# H3BR61_Hardware.net
KiCad netlist of a schematic drawn in EAGLE
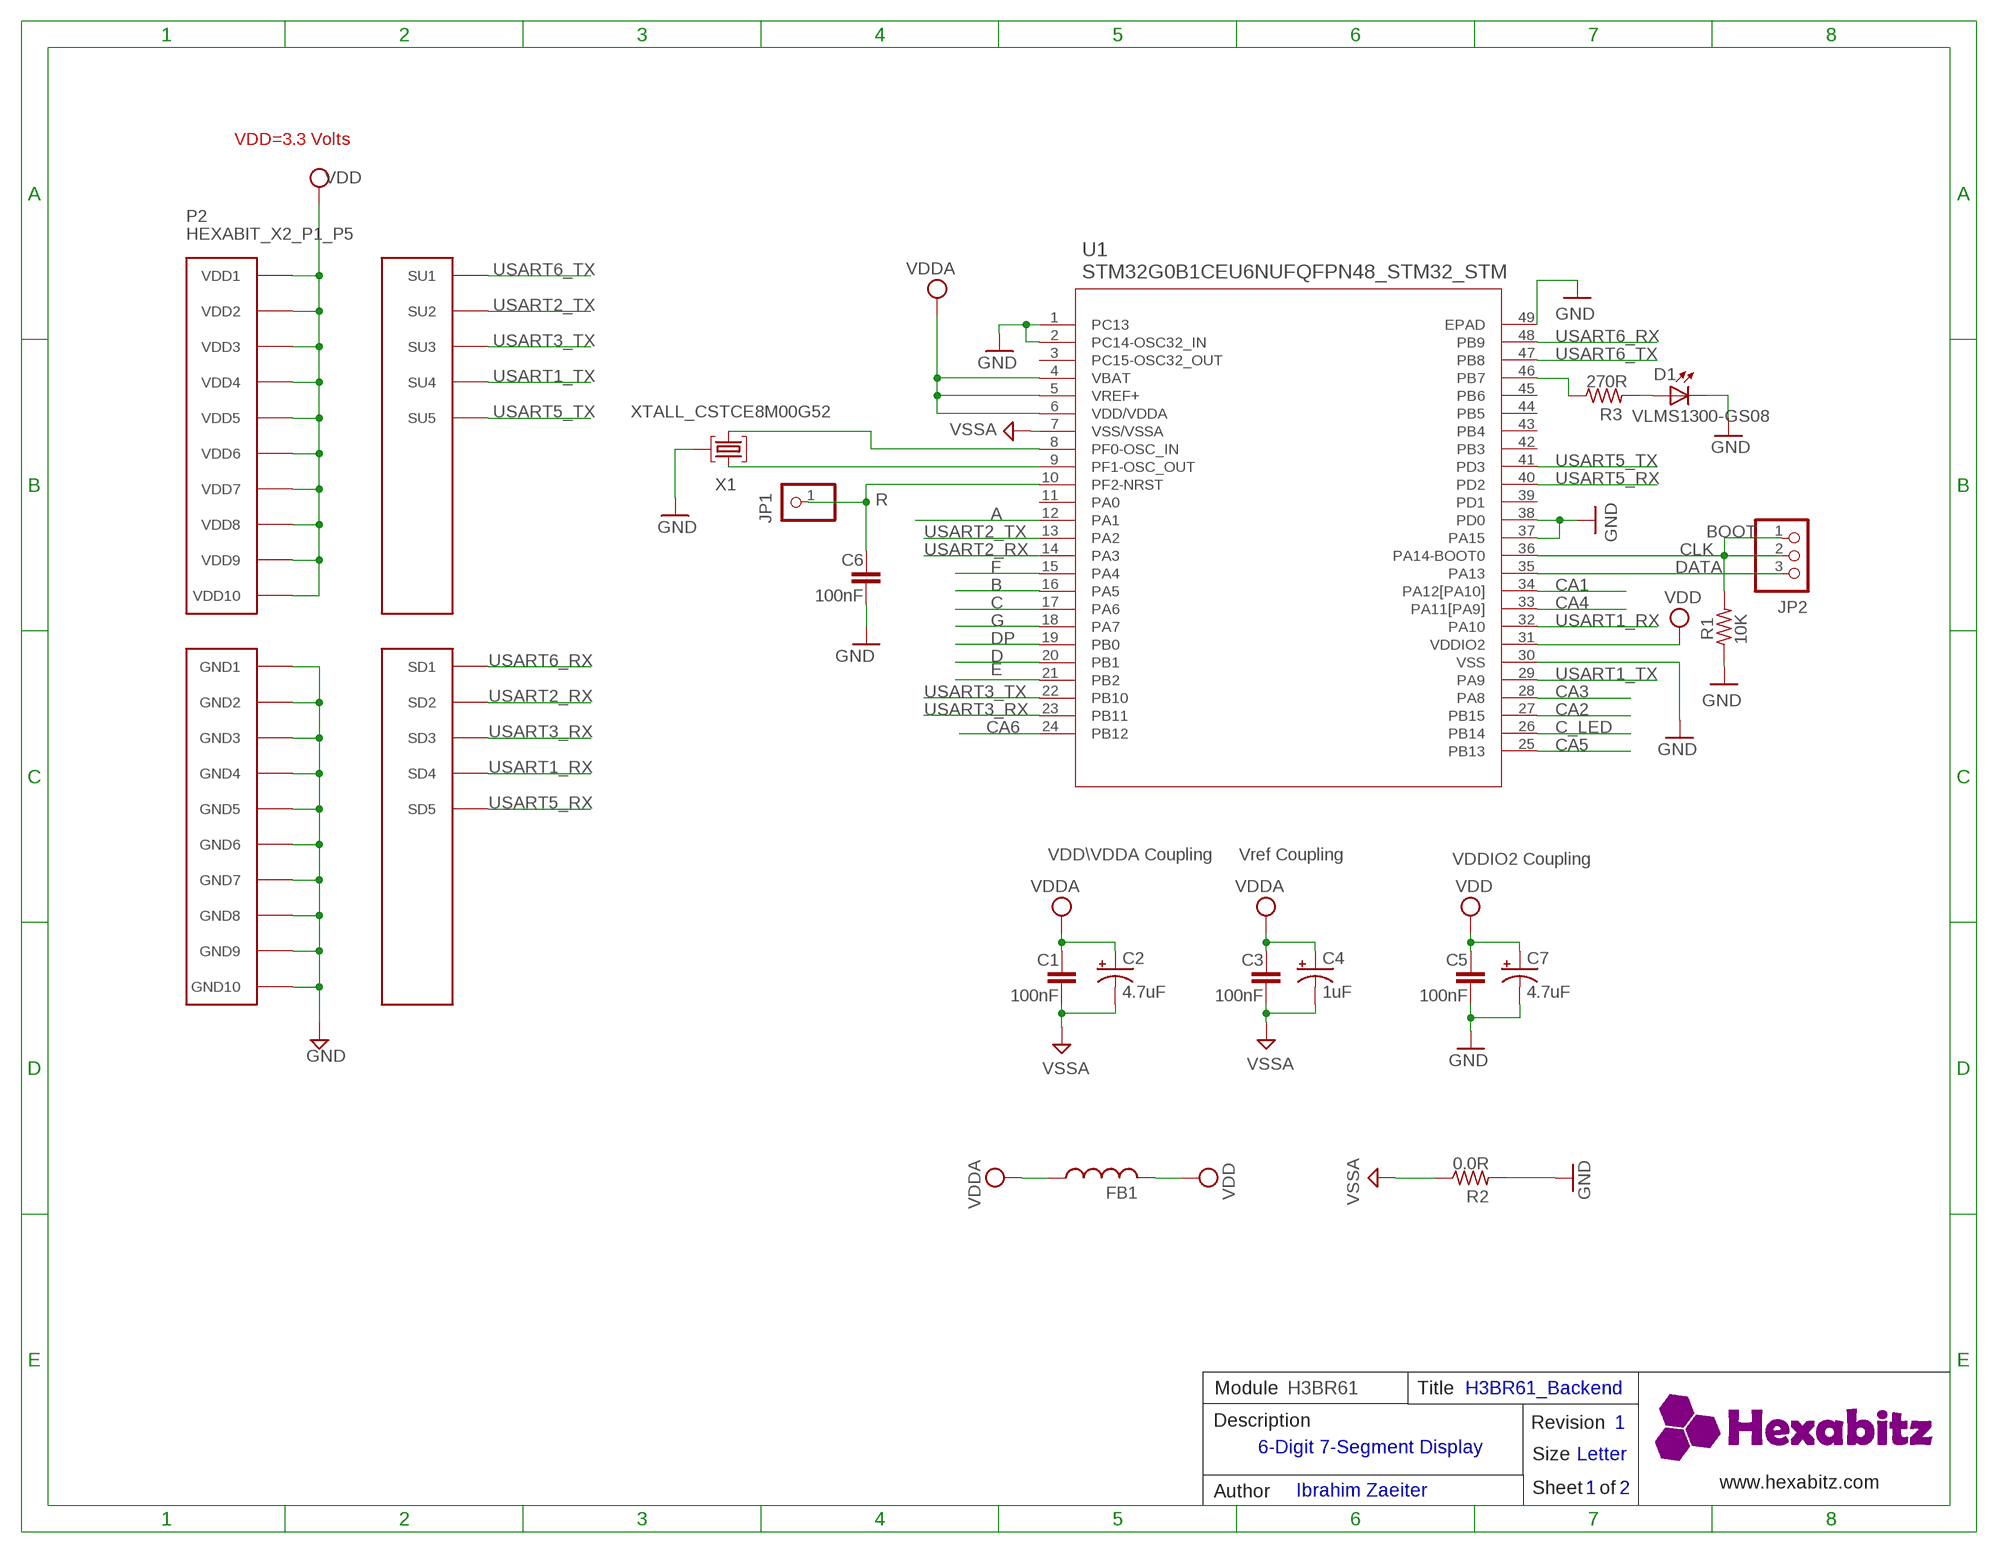
[diagram p0: schematic, sheet 1]
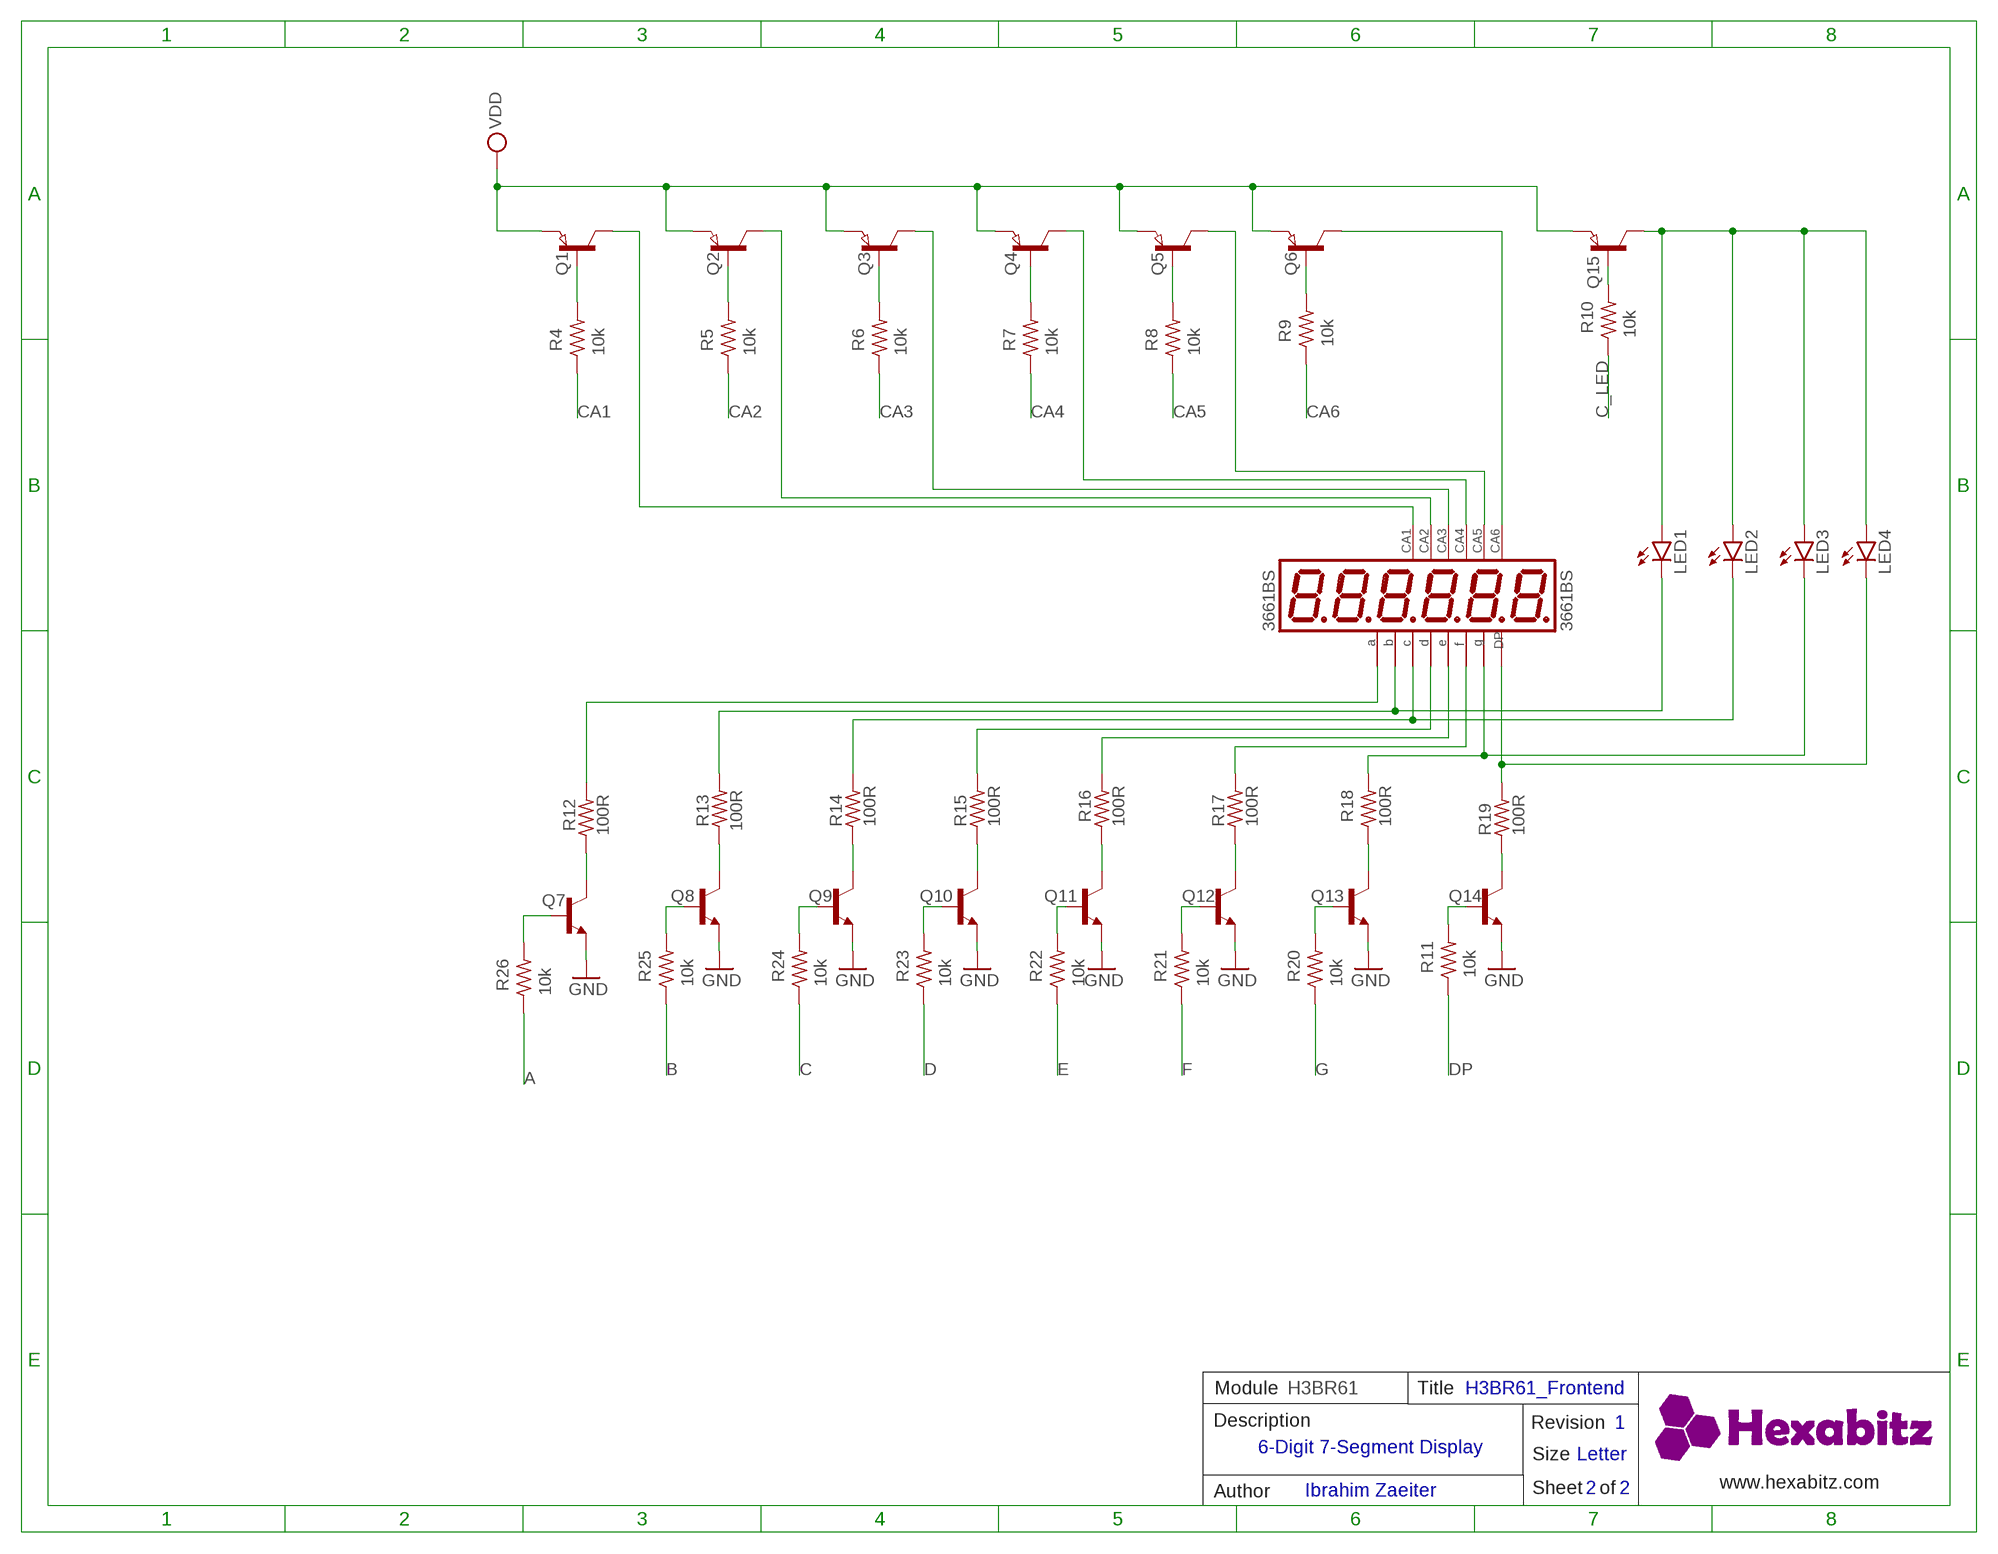
[diagram p1: schematic, sheet 2]

(export (version "E")
  (design (tool "Eeschema 10.0.6"))
  (components
    (comp (ref "C1")
      (value "100nF")
      (footprint "eagle-import:C-0603")
      (libsource (lib "eagle-import") (part "C-0603"))
    )
    (comp (ref "C2")
      (value "4.7uF")
      (footprint "eagle-import:C-0805-POL")
      (libsource (lib "eagle-import") (part "C-0805-POL"))
    )
    (comp (ref "C3")
      (value "100nF")
      (footprint "eagle-import:C-0603")
      (libsource (lib "eagle-import") (part "C-0603"))
    )
    (comp (ref "C4")
      (value "1uF")
      (footprint "eagle-import:C-0805-POL")
      (libsource (lib "eagle-import") (part "C-0805-POL"))
    )
    (comp (ref "C5")
      (value "100nF")
      (footprint "eagle-import:C-0603")
      (libsource (lib "eagle-import") (part "C-0603"))
    )
    (comp (ref "C6")
      (value "100nF")
      (footprint "eagle-import:C-0603")
      (libsource (lib "eagle-import") (part "C-0603"))
    )
    (comp (ref "C7")
      (value "4.7uF")
      (footprint "eagle-import:C-0805-POL")
      (libsource (lib "eagle-import") (part "C-0805-POL"))
    )
    (comp (ref "D1")
      (value "VLMS1300-GS08")
      (footprint "eagle-import:VLMS1300-GS08")
      (fields
        (field (name "MFN") "Vishay")
        (field (name "MPN") "VLMS1300-GS08")
        (field (name "OCTOPART_URL") "https://octopart.com/vlms1300-gs08-vishay-21709201?r=sp&s=_gcP4_q8T1SC6PJQPTQ9yA")
      )
      (libsource (lib "eagle-import") (part "VLMS1300-GS08"))
    )
    (comp (ref "FB1")
      (value "FB-0603")
      (footprint "eagle-import:FB-0603")
      (libsource (lib "eagle-import") (part "FB-0603"))
    )
    (comp (ref "JP1")
      (value "R")
      (footprint "eagle-import:1X01")
      (fields (field (name "MPN") "87227-1"))
      (libsource (lib "eagle-import") (part "PINHD-1X1"))
    )
    (comp (ref "JP2")
      (value "PINHD-1X3")
      (footprint "eagle-import:1X03")
      (libsource (lib "eagle-import") (part "PINHD-1X3"))
    )
    (comp (ref "P2")
      (value "HEXABIT_X2_P1_P5")
      (footprint "eagle-import:HEXABIT_17.32_X2_P1_P5")
      (libsource (lib "eagle-import") (part "HEXABIT_X2_P1_P5"))
    )
    (comp (ref "R1")
      (value "10K")
      (footprint "eagle-import:R-0603")
      (libsource (lib "eagle-import") (part "R-0603"))
    )
    (comp (ref "R2")
      (value "0.0R")
      (footprint "eagle-import:R-0603")
      (libsource (lib "eagle-import") (part "R-0603"))
    )
    (comp (ref "R3")
      (value "270R")
      (footprint "eagle-import:R-0603")
      (libsource (lib "eagle-import") (part "R-0603"))
    )
    (comp (ref "U1")
      (value "STM32G0B1CEU6NUFQFPN48_STM32_STM")
      (footprint "eagle-import:UFQFPN48_STM32_STM")
      (fields
        (field (name "MPN") "STM32G0B1CEU6N")
        (field (name "COPYRIGHT") "Copyright (C) 2022 Ultra Librarian. All rights reserved.")
      )
      (libsource (lib "eagle-import") (part "STM32G0B1CEU6NUFQFPN48_STM32_STM"))
    )
    (comp (ref "X1")
      (value "XTALL_CSTCE8M00G52")
      (footprint "eagle-import:XTALL_CSTCE8M00G52")
      (fields (field (name "MPN") "CSTCE8M00G52Z-R0"))
      (libsource (lib "eagle-import") (part "XTALL_CSTCE8M00G52"))
    )
    (comp (ref "3661BS")
      (value "3661BS")
      (footprint "eagle-import:3661BS")
      (libsource (lib "eagle-import") (part "3661BS"))
    )
    (comp (ref "LED1")
      (value "LED3MM")
      (footprint "eagle-import:LED3MM")
      (libsource (lib "eagle-import") (part "LED3MM"))
    )
    (comp (ref "LED2")
      (value "LED3MM")
      (footprint "eagle-import:LED3MM")
      (libsource (lib "eagle-import") (part "LED3MM"))
    )
    (comp (ref "LED3")
      (value "LED3MM")
      (footprint "eagle-import:LED3MM")
      (libsource (lib "eagle-import") (part "LED3MM"))
    )
    (comp (ref "LED4")
      (value "LED3MM")
      (footprint "eagle-import:LED3MM")
      (libsource (lib "eagle-import") (part "LED3MM"))
    )
    (comp (ref "Q1")
      (value "SEMICON-SMD-IPC_PNP-TRANSISTOR_SOT23")
      (footprint "eagle-import:SEMICON-SMD-IPC_SOT23")
      (libsource (lib "eagle-import") (part "SEMICON-SMD-IPC_PNP-TRANSISTOR_SOT23"))
    )
    (comp (ref "Q2")
      (value "SEMICON-SMD-IPC_PNP-TRANSISTOR_SOT23")
      (footprint "eagle-import:SEMICON-SMD-IPC_SOT23")
      (libsource (lib "eagle-import") (part "SEMICON-SMD-IPC_PNP-TRANSISTOR_SOT23"))
    )
    (comp (ref "Q3")
      (value "SEMICON-SMD-IPC_PNP-TRANSISTOR_SOT23")
      (footprint "eagle-import:SEMICON-SMD-IPC_SOT23")
      (libsource (lib "eagle-import") (part "SEMICON-SMD-IPC_PNP-TRANSISTOR_SOT23"))
    )
    (comp (ref "Q4")
      (value "SEMICON-SMD-IPC_PNP-TRANSISTOR_SOT23")
      (footprint "eagle-import:SEMICON-SMD-IPC_SOT23")
      (libsource (lib "eagle-import") (part "SEMICON-SMD-IPC_PNP-TRANSISTOR_SOT23"))
    )
    (comp (ref "Q5")
      (value "SEMICON-SMD-IPC_PNP-TRANSISTOR_SOT23")
      (footprint "eagle-import:SEMICON-SMD-IPC_SOT23")
      (libsource (lib "eagle-import") (part "SEMICON-SMD-IPC_PNP-TRANSISTOR_SOT23"))
    )
    (comp (ref "Q6")
      (value "SEMICON-SMD-IPC_PNP-TRANSISTOR_SOT23")
      (footprint "eagle-import:SEMICON-SMD-IPC_SOT23")
      (libsource (lib "eagle-import") (part "SEMICON-SMD-IPC_PNP-TRANSISTOR_SOT23"))
    )
    (comp (ref "Q7")
      (value "MMBT3904LT1")
      (footprint "eagle-import:MMBT3904LT1")
      (libsource (lib "eagle-import") (part "MMBT3904LT1"))
    )
    (comp (ref "Q8")
      (value "MMBT3904LT1")
      (footprint "eagle-import:MMBT3904LT1")
      (libsource (lib "eagle-import") (part "MMBT3904LT1"))
    )
    (comp (ref "Q9")
      (value "MMBT3904LT1")
      (footprint "eagle-import:MMBT3904LT1")
      (libsource (lib "eagle-import") (part "MMBT3904LT1"))
    )
    (comp (ref "Q10")
      (value "MMBT3904LT1")
      (footprint "eagle-import:MMBT3904LT1")
      (libsource (lib "eagle-import") (part "MMBT3904LT1"))
    )
    (comp (ref "Q11")
      (value "MMBT3904LT1")
      (footprint "eagle-import:MMBT3904LT1")
      (libsource (lib "eagle-import") (part "MMBT3904LT1"))
    )
    (comp (ref "Q12")
      (value "MMBT3904LT1")
      (footprint "eagle-import:MMBT3904LT1")
      (libsource (lib "eagle-import") (part "MMBT3904LT1"))
    )
    (comp (ref "Q13")
      (value "MMBT3904LT1")
      (footprint "eagle-import:MMBT3904LT1")
      (libsource (lib "eagle-import") (part "MMBT3904LT1"))
    )
    (comp (ref "Q14")
      (value "MMBT3904LT1")
      (footprint "eagle-import:MMBT3904LT1")
      (libsource (lib "eagle-import") (part "MMBT3904LT1"))
    )
    (comp (ref "Q15")
      (value "SEMICON-SMD-IPC_PNP-TRANSISTOR_SOT23")
      (footprint "eagle-import:SEMICON-SMD-IPC_SOT23")
      (libsource (lib "eagle-import") (part "SEMICON-SMD-IPC_PNP-TRANSISTOR_SOT23"))
    )
    (comp (ref "R4")
      (value "10k")
      (footprint "eagle-import:R-0603")
      (libsource (lib "eagle-import") (part "R-0603"))
    )
    (comp (ref "R5")
      (value "10k")
      (footprint "eagle-import:R-0603")
      (libsource (lib "eagle-import") (part "R-0603"))
    )
    (comp (ref "R6")
      (value "10k")
      (footprint "eagle-import:R-0603")
      (libsource (lib "eagle-import") (part "R-0603"))
    )
    (comp (ref "R7")
      (value "10k")
      (footprint "eagle-import:R-0603")
      (libsource (lib "eagle-import") (part "R-0603"))
    )
    (comp (ref "R8")
      (value "10k")
      (footprint "eagle-import:R-0603")
      (libsource (lib "eagle-import") (part "R-0603"))
    )
    (comp (ref "R9")
      (value "10k")
      (footprint "eagle-import:R-0603")
      (libsource (lib "eagle-import") (part "R-0603"))
    )
    (comp (ref "R10")
      (value "10k")
      (footprint "eagle-import:R-0603")
      (libsource (lib "eagle-import") (part "R-0603"))
    )
    (comp (ref "R11")
      (value "10k")
      (footprint "eagle-import:R-0603")
      (libsource (lib "eagle-import") (part "R-0603"))
    )
    (comp (ref "R12")
      (value "100R")
      (footprint "eagle-import:R-0603")
      (libsource (lib "eagle-import") (part "R-0603"))
    )
    (comp (ref "R13")
      (value "100R")
      (footprint "eagle-import:R-0603")
      (libsource (lib "eagle-import") (part "R-0603"))
    )
    (comp (ref "R14")
      (value "100R")
      (footprint "eagle-import:R-0603")
      (libsource (lib "eagle-import") (part "R-0603"))
    )
    (comp (ref "R15")
      (value "100R")
      (footprint "eagle-import:R-0603")
      (libsource (lib "eagle-import") (part "R-0603"))
    )
    (comp (ref "R16")
      (value "100R")
      (footprint "eagle-import:R-0603")
      (libsource (lib "eagle-import") (part "R-0603"))
    )
    (comp (ref "R17")
      (value "100R")
      (footprint "eagle-import:R-0603")
      (libsource (lib "eagle-import") (part "R-0603"))
    )
    (comp (ref "R18")
      (value "100R")
      (footprint "eagle-import:R-0603")
      (libsource (lib "eagle-import") (part "R-0603"))
    )
    (comp (ref "R19")
      (value "100R")
      (footprint "eagle-import:R-0603")
      (libsource (lib "eagle-import") (part "R-0603"))
    )
    (comp (ref "R20")
      (value "10k")
      (footprint "eagle-import:R-0603")
      (libsource (lib "eagle-import") (part "R-0603"))
    )
    (comp (ref "R21")
      (value "10k")
      (footprint "eagle-import:R-0603")
      (libsource (lib "eagle-import") (part "R-0603"))
    )
    (comp (ref "R22")
      (value "10k")
      (footprint "eagle-import:R-0603")
      (libsource (lib "eagle-import") (part "R-0603"))
    )
    (comp (ref "R23")
      (value "10k")
      (footprint "eagle-import:R-0603")
      (libsource (lib "eagle-import") (part "R-0603"))
    )
    (comp (ref "R24")
      (value "10k")
      (footprint "eagle-import:R-0603")
      (libsource (lib "eagle-import") (part "R-0603"))
    )
    (comp (ref "R25")
      (value "10k")
      (footprint "eagle-import:R-0603")
      (libsource (lib "eagle-import") (part "R-0603"))
    )
    (comp (ref "R26")
      (value "10k")
      (footprint "eagle-import:R-0603")
      (libsource (lib "eagle-import") (part "R-0603"))
    )
  )
  (nets
    (net (code "1") (name "A") (class "Default")
      (node (ref "R26") (pin "1") (pinfunction "1_1") (pintype "passive"))
      (node (ref "U1") (pin "12") (pinfunction "PA1_12") (pintype "bidirectional"))
    )
    (net (code "2") (name "B") (class "Default")
      (node (ref "R25") (pin "1") (pinfunction "1_1") (pintype "passive"))
      (node (ref "U1") (pin "16") (pinfunction "PA5_16") (pintype "bidirectional"))
    )
    (net (code "3") (name "C") (class "Default")
      (node (ref "R24") (pin "1") (pinfunction "1_1") (pintype "passive"))
      (node (ref "U1") (pin "17") (pinfunction "PA6_17") (pintype "bidirectional"))
    )
    (net (code "4") (name "CA1") (class "Default")
      (node (ref "R4") (pin "1") (pinfunction "1_1") (pintype "passive"))
      (node (ref "U1") (pin "34") (pinfunction "PA12[PA10]_34") (pintype "bidirectional"))
    )
    (net (code "5") (name "CA2") (class "Default")
      (node (ref "R5") (pin "1") (pinfunction "1_1") (pintype "passive"))
      (node (ref "U1") (pin "27") (pinfunction "PB15_27") (pintype "bidirectional"))
    )
    (net (code "6") (name "CA3") (class "Default")
      (node (ref "R6") (pin "1") (pinfunction "1_1") (pintype "passive"))
      (node (ref "U1") (pin "28") (pinfunction "PA8_28") (pintype "bidirectional"))
    )
    (net (code "7") (name "CA4") (class "Default")
      (node (ref "R7") (pin "1") (pinfunction "1_1") (pintype "passive"))
      (node (ref "U1") (pin "33") (pinfunction "PA11[PA9]_33") (pintype "bidirectional"))
    )
    (net (code "8") (name "CA5") (class "Default")
      (node (ref "R8") (pin "1") (pinfunction "1_1") (pintype "passive"))
      (node (ref "U1") (pin "25") (pinfunction "PB13_25") (pintype "bidirectional"))
    )
    (net (code "9") (name "CA6") (class "Default")
      (node (ref "R9") (pin "1") (pinfunction "1_1") (pintype "passive"))
      (node (ref "U1") (pin "24") (pinfunction "PB12_24") (pintype "bidirectional"))
    )
    (net (code "10") (name "CLK") (class "Default")
      (node (ref "JP2") (pin "1") (pinfunction "1_1") (pintype "passive"))
      (node (ref "JP2") (pin "2") (pinfunction "2_2") (pintype "passive"))
      (node (ref "R1") (pin "2") (pinfunction "2_2") (pintype "passive"))
      (node (ref "U1") (pin "36") (pinfunction "PA14-BOOT0_36") (pintype "bidirectional"))
    )
    (net (code "11") (name "C_LED") (class "Default")
      (node (ref "R10") (pin "1") (pinfunction "1_1") (pintype "passive"))
      (node (ref "U1") (pin "26") (pinfunction "PB14_26") (pintype "bidirectional"))
    )
    (net (code "12") (name "D") (class "Default")
      (node (ref "R23") (pin "1") (pinfunction "1_1") (pintype "passive"))
      (node (ref "U1") (pin "20") (pinfunction "PB1_20") (pintype "bidirectional"))
    )
    (net (code "13") (name "DATA") (class "Default")
      (node (ref "JP2") (pin "3") (pinfunction "3_3") (pintype "passive"))
      (node (ref "U1") (pin "35") (pinfunction "PA13_35") (pintype "bidirectional"))
    )
    (net (code "14") (name "DP") (class "Default")
      (node (ref "R11") (pin "1") (pinfunction "1_1") (pintype "passive"))
      (node (ref "U1") (pin "19") (pinfunction "PB0_19") (pintype "bidirectional"))
    )
    (net (code "15") (name "E") (class "Default")
      (node (ref "R22") (pin "1") (pinfunction "1_1") (pintype "passive"))
      (node (ref "U1") (pin "21") (pinfunction "PB2_21") (pintype "bidirectional"))
    )
    (net (code "16") (name "F") (class "Default")
      (node (ref "R21") (pin "1") (pinfunction "1_1") (pintype "passive"))
      (node (ref "U1") (pin "15") (pinfunction "PA4_15") (pintype "bidirectional"))
    )
    (net (code "17") (name "G") (class "Default")
      (node (ref "R20") (pin "1") (pinfunction "1_1") (pintype "passive"))
      (node (ref "U1") (pin "18") (pinfunction "PA7_18") (pintype "bidirectional"))
    )
    (net (code "18") (name "GND") (class "Default")
      (node (ref "C5") (pin "2") (pinfunction "2_2") (pintype "passive"))
      (node (ref "C6") (pin "2") (pinfunction "2_2") (pintype "passive"))
      (node (ref "C7") (pin "2") (pinfunction "-_2") (pintype "passive"))
      (node (ref "D1") (pin "C") (pinfunction "C_C") (pintype "passive"))
      (node (ref "P2") (pin "PAD_PD11") (pinfunction "GND1_PAD_PD11") (pintype "power_in"))
      (node (ref "P2") (pin "PAD_PD12") (pinfunction "GND2_PAD_PD12") (pintype "power_in"))
      (node (ref "P2") (pin "PAD_PD13") (pinfunction "GND3_PAD_PD13") (pintype "power_in"))
      (node (ref "P2") (pin "PAD_PD14") (pinfunction "GND4_PAD_PD14") (pintype "power_in"))
      (node (ref "P2") (pin "PAD_PD15") (pinfunction "GND5_PAD_PD15") (pintype "power_in"))
      (node (ref "P2") (pin "PAD_PD16") (pinfunction "GND6_PAD_PD16") (pintype "power_in"))
      (node (ref "P2") (pin "PAD_PD17") (pinfunction "GND7_PAD_PD17") (pintype "power_in"))
      (node (ref "P2") (pin "PAD_PD18") (pinfunction "GND8_PAD_PD18") (pintype "power_in"))
      (node (ref "P2") (pin "PAD_PD19") (pinfunction "GND9_PAD_PD19") (pintype "power_in"))
      (node (ref "P2") (pin "PAD_PD20") (pinfunction "GND10_PAD_PD20") (pintype "power_in"))
      (node (ref "Q10") (pin "2") (pinfunction "E_2") (pintype "passive"))
      (node (ref "Q11") (pin "2") (pinfunction "E_2") (pintype "passive"))
      (node (ref "Q12") (pin "2") (pinfunction "E_2") (pintype "passive"))
      (node (ref "Q13") (pin "2") (pinfunction "E_2") (pintype "passive"))
      (node (ref "Q14") (pin "2") (pinfunction "E_2") (pintype "passive"))
      (node (ref "Q7") (pin "2") (pinfunction "E_2") (pintype "passive"))
      (node (ref "Q8") (pin "2") (pinfunction "E_2") (pintype "passive"))
      (node (ref "Q9") (pin "2") (pinfunction "E_2") (pintype "passive"))
      (node (ref "R1") (pin "1") (pinfunction "1_1") (pintype "passive"))
      (node (ref "R2") (pin "2") (pinfunction "2_2") (pintype "passive"))
      (node (ref "U1") (pin "1") (pinfunction "PC13_1") (pintype "bidirectional"))
      (node (ref "U1") (pin "2") (pinfunction "PC14-OSC32_IN_2") (pintype "bidirectional"))
      (node (ref "U1") (pin "30") (pinfunction "VSS_30") (pintype "passive"))
      (node (ref "U1") (pin "37") (pinfunction "PA15_37") (pintype "bidirectional"))
      (node (ref "U1") (pin "38") (pinfunction "PD0_38") (pintype "bidirectional"))
      (node (ref "U1") (pin "49") (pinfunction "EPAD_49") (pintype "passive"))
      (node (ref "X1") (pin "P$2") (pinfunction "2_P$2") (pintype "passive"))
    )
    (net (code "19") (name "Net-(3661BS-A)") (class "Default")
      (node (ref "3661BS") (pin "13") (pinfunction "A_13") (pintype "passive"))
      (node (ref "R12") (pin "2") (pinfunction "2_2") (pintype "passive"))
    )
    (net (code "20") (name "Net-(3661BS-B)") (class "Default")
      (node (ref "3661BS") (pin "9") (pinfunction "B_9") (pintype "passive"))
      (node (ref "LED1") (pin "K") (pinfunction "C_K") (pintype "passive"))
      (node (ref "R13") (pin "2") (pinfunction "2_2") (pintype "passive"))
    )
    (net (code "21") (name "Net-(3661BS-C)") (class "Default")
      (node (ref "3661BS") (pin "4") (pinfunction "C_4") (pintype "passive"))
      (node (ref "LED2") (pin "K") (pinfunction "C_K") (pintype "passive"))
      (node (ref "R14") (pin "2") (pinfunction "2_2") (pintype "passive"))
    )
    (net (code "22") (name "Net-(3661BS-D)") (class "Default")
      (node (ref "3661BS") (pin "2") (pinfunction "D_2") (pintype "passive"))
      (node (ref "R15") (pin "2") (pinfunction "2_2") (pintype "passive"))
    )
    (net (code "23") (name "Net-(3661BS-DP)") (class "Default")
      (node (ref "3661BS") (pin "3") (pinfunction "DP_3") (pintype "passive"))
      (node (ref "LED4") (pin "K") (pinfunction "C_K") (pintype "passive"))
      (node (ref "R19") (pin "2") (pinfunction "2_2") (pintype "passive"))
    )
    (net (code "24") (name "Net-(3661BS-E)") (class "Default")
      (node (ref "3661BS") (pin "1") (pinfunction "E_1") (pintype "passive"))
      (node (ref "R16") (pin "2") (pinfunction "2_2") (pintype "passive"))
    )
    (net (code "25") (name "Net-(3661BS-F)") (class "Default")
      (node (ref "3661BS") (pin "12") (pinfunction "F_12") (pintype "passive"))
      (node (ref "R17") (pin "2") (pinfunction "2_2") (pintype "passive"))
    )
    (net (code "26") (name "Net-(3661BS-G)") (class "Default")
      (node (ref "3661BS") (pin "5") (pinfunction "G_5") (pintype "passive"))
      (node (ref "LED3") (pin "K") (pinfunction "C_K") (pintype "passive"))
      (node (ref "R18") (pin "2") (pinfunction "2_2") (pintype "passive"))
    )
    (net (code "27") (name "Net-(D1-PadA)") (class "Default")
      (node (ref "D1") (pin "A") (pinfunction "A_A") (pintype "passive"))
      (node (ref "R3") (pin "2") (pinfunction "2_2") (pintype "passive"))
    )
    (net (code "28") (name "Net-(Q1-B)") (class "Default")
      (node (ref "Q1") (pin "1") (pinfunction "B_1") (pintype "passive"))
      (node (ref "R4") (pin "2") (pinfunction "2_2") (pintype "passive"))
    )
    (net (code "29") (name "Net-(Q1-C)") (class "Default")
      (node (ref "3661BS") (pin "14") (pinfunction "CA_14") (pintype "passive"))
      (node (ref "Q1") (pin "3") (pinfunction "C_3") (pintype "passive"))
    )
    (net (code "30") (name "Net-(Q2-B)") (class "Default")
      (node (ref "Q2") (pin "1") (pinfunction "B_1") (pintype "passive"))
      (node (ref "R5") (pin "2") (pinfunction "2_2") (pintype "passive"))
    )
    (net (code "31") (name "Net-(Q2-C)") (class "Default")
      (node (ref "3661BS") (pin "11") (pinfunction "CA_11") (pintype "passive"))
      (node (ref "Q2") (pin "3") (pinfunction "C_3") (pintype "passive"))
    )
    (net (code "32") (name "Net-(Q3-B)") (class "Default")
      (node (ref "Q3") (pin "1") (pinfunction "B_1") (pintype "passive"))
      (node (ref "R6") (pin "2") (pinfunction "2_2") (pintype "passive"))
    )
    (net (code "33") (name "Net-(Q3-C)") (class "Default")
      (node (ref "3661BS") (pin "10") (pinfunction "CA_10") (pintype "passive"))
      (node (ref "Q3") (pin "3") (pinfunction "C_3") (pintype "passive"))
    )
    (net (code "34") (name "Net-(Q4-B)") (class "Default")
      (node (ref "Q4") (pin "1") (pinfunction "B_1") (pintype "passive"))
      (node (ref "R7") (pin "2") (pinfunction "2_2") (pintype "passive"))
    )
    (net (code "35") (name "Net-(Q4-C)") (class "Default")
      (node (ref "3661BS") (pin "8") (pinfunction "CA_8") (pintype "passive"))
      (node (ref "Q4") (pin "3") (pinfunction "C_3") (pintype "passive"))
    )
    (net (code "36") (name "Net-(Q5-B)") (class "Default")
      (node (ref "Q5") (pin "1") (pinfunction "B_1") (pintype "passive"))
      (node (ref "R8") (pin "2") (pinfunction "2_2") (pintype "passive"))
    )
    (net (code "37") (name "Net-(Q5-C)") (class "Default")
      (node (ref "3661BS") (pin "6") (pinfunction "CA_6") (pintype "passive"))
      (node (ref "Q5") (pin "3") (pinfunction "C_3") (pintype "passive"))
    )
    (net (code "38") (name "Net-(Q6-B)") (class "Default")
      (node (ref "Q6") (pin "1") (pinfunction "B_1") (pintype "passive"))
      (node (ref "R9") (pin "2") (pinfunction "2_2") (pintype "passive"))
    )
    (net (code "39") (name "Net-(Q6-C)") (class "Default")
      (node (ref "3661BS") (pin "7") (pinfunction "CA_7") (pintype "passive"))
      (node (ref "Q6") (pin "3") (pinfunction "C_3") (pintype "passive"))
    )
    (net (code "40") (name "Net-(Q7-B)") (class "Default")
      (node (ref "Q7") (pin "1") (pinfunction "B_1") (pintype "passive"))
      (node (ref "R26") (pin "2") (pinfunction "2_2") (pintype "passive"))
    )
    (net (code "41") (name "Net-(Q7-C)") (class "Default")
      (node (ref "Q7") (pin "3") (pinfunction "C_3") (pintype "passive"))
      (node (ref "R12") (pin "1") (pinfunction "1_1") (pintype "passive"))
    )
    (net (code "42") (name "Net-(Q8-B)") (class "Default")
      (node (ref "Q8") (pin "1") (pinfunction "B_1") (pintype "passive"))
      (node (ref "R25") (pin "2") (pinfunction "2_2") (pintype "passive"))
    )
    (net (code "43") (name "Net-(Q8-C)") (class "Default")
      (node (ref "Q8") (pin "3") (pinfunction "C_3") (pintype "passive"))
      (node (ref "R13") (pin "1") (pinfunction "1_1") (pintype "passive"))
    )
    (net (code "44") (name "Net-(Q9-B)") (class "Default")
      (node (ref "Q9") (pin "1") (pinfunction "B_1") (pintype "passive"))
      (node (ref "R24") (pin "2") (pinfunction "2_2") (pintype "passive"))
    )
    (net (code "45") (name "Net-(Q9-C)") (class "Default")
      (node (ref "Q9") (pin "3") (pinfunction "C_3") (pintype "passive"))
      (node (ref "R14") (pin "1") (pinfunction "1_1") (pintype "passive"))
    )
    (net (code "46") (name "Net-(Q10-B)") (class "Default")
      (node (ref "Q10") (pin "1") (pinfunction "B_1") (pintype "passive"))
      (node (ref "R23") (pin "2") (pinfunction "2_2") (pintype "passive"))
    )
    (net (code "47") (name "Net-(Q10-C)") (class "Default")
      (node (ref "Q10") (pin "3") (pinfunction "C_3") (pintype "passive"))
      (node (ref "R15") (pin "1") (pinfunction "1_1") (pintype "passive"))
    )
    (net (code "48") (name "Net-(Q11-B)") (class "Default")
      (node (ref "Q11") (pin "1") (pinfunction "B_1") (pintype "passive"))
      (node (ref "R22") (pin "2") (pinfunction "2_2") (pintype "passive"))
    )
    (net (code "49") (name "Net-(Q11-C)") (class "Default")
      (node (ref "Q11") (pin "3") (pinfunction "C_3") (pintype "passive"))
      (node (ref "R16") (pin "1") (pinfunction "1_1") (pintype "passive"))
    )
    (net (code "50") (name "Net-(Q12-B)") (class "Default")
      (node (ref "Q12") (pin "1") (pinfunction "B_1") (pintype "passive"))
      (node (ref "R21") (pin "2") (pinfunction "2_2") (pintype "passive"))
    )
    (net (code "51") (name "Net-(Q12-C)") (class "Default")
      (node (ref "Q12") (pin "3") (pinfunction "C_3") (pintype "passive"))
      (node (ref "R17") (pin "1") (pinfunction "1_1") (pintype "passive"))
    )
    (net (code "52") (name "Net-(Q13-B)") (class "Default")
      (node (ref "Q13") (pin "1") (pinfunction "B_1") (pintype "passive"))
      (node (ref "R20") (pin "2") (pinfunction "2_2") (pintype "passive"))
    )
    (net (code "53") (name "Net-(Q13-C)") (class "Default")
      (node (ref "Q13") (pin "3") (pinfunction "C_3") (pintype "passive"))
      (node (ref "R18") (pin "1") (pinfunction "1_1") (pintype "passive"))
    )
    (net (code "54") (name "Net-(Q14-B)") (class "Default")
      (node (ref "Q14") (pin "1") (pinfunction "B_1") (pintype "passive"))
      (node (ref "R11") (pin "2") (pinfunction "2_2") (pintype "passive"))
    )
    (net (code "55") (name "Net-(Q14-C)") (class "Default")
      (node (ref "Q14") (pin "3") (pinfunction "C_3") (pintype "passive"))
      (node (ref "R19") (pin "1") (pinfunction "1_1") (pintype "passive"))
    )
    (net (code "56") (name "Net-(Q15-B)") (class "Default")
      (node (ref "Q15") (pin "1") (pinfunction "B_1") (pintype "passive"))
      (node (ref "R10") (pin "2") (pinfunction "2_2") (pintype "passive"))
    )
    (net (code "57") (name "Net-(Q15-C)") (class "Default")
      (node (ref "LED1") (pin "A") (pinfunction "A_A") (pintype "passive"))
      (node (ref "LED2") (pin "A") (pinfunction "A_A") (pintype "passive"))
      (node (ref "LED3") (pin "A") (pinfunction "A_A") (pintype "passive"))
      (node (ref "LED4") (pin "A") (pinfunction "A_A") (pintype "passive"))
      (node (ref "Q15") (pin "3") (pinfunction "C_3") (pintype "passive"))
    )
    (net (code "58") (name "Net-(U1-PB7)") (class "Default")
      (node (ref "R3") (pin "1") (pinfunction "1_1") (pintype "passive"))
      (node (ref "U1") (pin "46") (pinfunction "PB7_46") (pintype "bidirectional"))
    )
    (net (code "59") (name "Net-(U1-PF0-OSC_IN)") (class "Default")
      (node (ref "U1") (pin "8") (pinfunction "PF0-OSC_IN_8") (pintype "bidirectional"))
      (node (ref "X1") (pin "P$3") (pinfunction "3_P$3") (pintype "passive"))
    )
    (net (code "60") (name "Net-(U1-PF1-OSC_OUT)") (class "Default")
      (node (ref "U1") (pin "9") (pinfunction "PF1-OSC_OUT_9") (pintype "bidirectional"))
      (node (ref "X1") (pin "P$1") (pinfunction "1_P$1") (pintype "passive"))
    )
    (net (code "61") (name "Net-(U1-PF2-NRST)") (class "Default")
      (node (ref "C6") (pin "1") (pinfunction "1_1") (pintype "passive"))
      (node (ref "JP1") (pin "1") (pinfunction "1_1") (pintype "passive"))
      (node (ref "U1") (pin "10") (pinfunction "PF2-NRST_10") (pintype "bidirectional"))
    )
    (net (code "62") (name "USART1_RX") (class "Default")
      (node (ref "P2") (pin "PAD_PD4") (pinfunction "SD4_PAD_PD4") (pintype "bidirectional"))
      (node (ref "U1") (pin "32") (pinfunction "PA10_32") (pintype "bidirectional"))
    )
    (net (code "63") (name "USART1_TX") (class "Default")
      (node (ref "P2") (pin "PAD_PU4") (pinfunction "SU4_PAD_PU4") (pintype "bidirectional"))
      (node (ref "U1") (pin "29") (pinfunction "PA9_29") (pintype "bidirectional"))
    )
    (net (code "64") (name "USART2_RX") (class "Default")
      (node (ref "P2") (pin "PAD_PD2") (pinfunction "SD2_PAD_PD2") (pintype "bidirectional"))
      (node (ref "U1") (pin "14") (pinfunction "PA3_14") (pintype "bidirectional"))
    )
    (net (code "65") (name "USART2_TX") (class "Default")
      (node (ref "P2") (pin "PAD_PU2") (pinfunction "SU2_PAD_PU2") (pintype "bidirectional"))
      (node (ref "U1") (pin "13") (pinfunction "PA2_13") (pintype "bidirectional"))
    )
    (net (code "66") (name "USART3_RX") (class "Default")
      (node (ref "P2") (pin "PAD_PD3") (pinfunction "SD3_PAD_PD3") (pintype "bidirectional"))
      (node (ref "U1") (pin "23") (pinfunction "PB11_23") (pintype "bidirectional"))
    )
    (net (code "67") (name "USART3_TX") (class "Default")
      (node (ref "P2") (pin "PAD_PU3") (pinfunction "SU3_PAD_PU3") (pintype "bidirectional"))
      (node (ref "U1") (pin "22") (pinfunction "PB10_22") (pintype "bidirectional"))
    )
    (net (code "68") (name "USART5_RX") (class "Default")
      (node (ref "P2") (pin "PAD_PD5") (pinfunction "SD5_PAD_PD5") (pintype "bidirectional"))
      (node (ref "U1") (pin "40") (pinfunction "PD2_40") (pintype "bidirectional"))
    )
    (net (code "69") (name "USART5_TX") (class "Default")
      (node (ref "P2") (pin "PAD_PU5") (pinfunction "SU5_PAD_PU5") (pintype "bidirectional"))
      (node (ref "U1") (pin "41") (pinfunction "PD3_41") (pintype "bidirectional"))
    )
    (net (code "70") (name "USART6_RX") (class "Default")
      (node (ref "P2") (pin "PAD_PD1") (pinfunction "SD1_PAD_PD1") (pintype "bidirectional"))
      (node (ref "U1") (pin "48") (pinfunction "PB9_48") (pintype "bidirectional"))
    )
    (net (code "71") (name "USART6_TX") (class "Default")
      (node (ref "P2") (pin "PAD_PU1") (pinfunction "SU1_PAD_PU1") (pintype "bidirectional"))
      (node (ref "U1") (pin "47") (pinfunction "PB8_47") (pintype "bidirectional"))
    )
    (net (code "72") (name "VDD") (class "Default")
      (node (ref "C5") (pin "1") (pinfunction "1_1") (pintype "passive"))
      (node (ref "C7") (pin "1") (pinfunction "+_1") (pintype "passive"))
      (node (ref "FB1") (pin "2") (pinfunction "2_2") (pintype "passive"))
      (node (ref "P2") (pin "PAD_PU11") (pinfunction "VDD1_PAD_PU11") (pintype "power_in"))
      (node (ref "P2") (pin "PAD_PU12") (pinfunction "VDD2_PAD_PU12") (pintype "power_in"))
      (node (ref "P2") (pin "PAD_PU13") (pinfunction "VDD3_PAD_PU13") (pintype "power_in"))
      (node (ref "P2") (pin "PAD_PU14") (pinfunction "VDD4_PAD_PU14") (pintype "power_in"))
      (node (ref "P2") (pin "PAD_PU15") (pinfunction "VDD5_PAD_PU15") (pintype "power_in"))
      (node (ref "P2") (pin "PAD_PU16") (pinfunction "VDD6_PAD_PU16") (pintype "power_in"))
      (node (ref "P2") (pin "PAD_PU17") (pinfunction "VDD7_PAD_PU17") (pintype "power_in"))
      (node (ref "P2") (pin "PAD_PU18") (pinfunction "VDD8_PAD_PU18") (pintype "power_in"))
      (node (ref "P2") (pin "PAD_PU19") (pinfunction "VDD9_PAD_PU19") (pintype "power_in"))
      (node (ref "P2") (pin "PAD_PU20") (pinfunction "VDD10_PAD_PU20") (pintype "power_in"))
      (node (ref "Q1") (pin "2") (pinfunction "E_2") (pintype "passive"))
      (node (ref "Q15") (pin "2") (pinfunction "E_2") (pintype "passive"))
      (node (ref "Q2") (pin "2") (pinfunction "E_2") (pintype "passive"))
      (node (ref "Q3") (pin "2") (pinfunction "E_2") (pintype "passive"))
      (node (ref "Q4") (pin "2") (pinfunction "E_2") (pintype "passive"))
      (node (ref "Q5") (pin "2") (pinfunction "E_2") (pintype "passive"))
      (node (ref "Q6") (pin "2") (pinfunction "E_2") (pintype "passive"))
      (node (ref "U1") (pin "31") (pinfunction "VDDIO2_31") (pintype "power_in"))
    )
    (net (code "73") (name "VDDA") (class "Default")
      (node (ref "C1") (pin "1") (pinfunction "1_1") (pintype "passive"))
      (node (ref "C2") (pin "1") (pinfunction "+_1") (pintype "passive"))
      (node (ref "C3") (pin "1") (pinfunction "1_1") (pintype "passive"))
      (node (ref "C4") (pin "1") (pinfunction "+_1") (pintype "passive"))
      (node (ref "FB1") (pin "1") (pinfunction "1_1") (pintype "passive"))
      (node (ref "U1") (pin "4") (pinfunction "VBAT_4") (pintype "power_in"))
      (node (ref "U1") (pin "5") (pinfunction "VREF+_5") (pintype "power_in"))
      (node (ref "U1") (pin "6") (pinfunction "VDD/VDDA_6") (pintype "power_in"))
    )
    (net (code "74") (name "VSSA") (class "Default")
      (node (ref "C1") (pin "2") (pinfunction "2_2") (pintype "passive"))
      (node (ref "C2") (pin "2") (pinfunction "-_2") (pintype "passive"))
      (node (ref "C3") (pin "2") (pinfunction "2_2") (pintype "passive"))
      (node (ref "C4") (pin "2") (pinfunction "-_2") (pintype "passive"))
      (node (ref "R2") (pin "1") (pinfunction "1_1") (pintype "passive"))
      (node (ref "U1") (pin "7") (pinfunction "VSS/VSSA_7") (pintype "passive"))
    )
    (net (code "75") (name "unconnected-(U1-PA0-Pad11)") (class "Default")
      (node (ref "U1") (pin "11") (pinfunction "PA0_11") (pintype "bidirectional"))
    )
    (net (code "76") (name "unconnected-(U1-PB3-Pad42)") (class "Default")
      (node (ref "U1") (pin "42") (pinfunction "PB3_42") (pintype "bidirectional"))
    )
    (net (code "77") (name "unconnected-(U1-PB4-Pad43)") (class "Default")
      (node (ref "U1") (pin "43") (pinfunction "PB4_43") (pintype "bidirectional"))
    )
    (net (code "78") (name "unconnected-(U1-PB5-Pad44)") (class "Default")
      (node (ref "U1") (pin "44") (pinfunction "PB5_44") (pintype "bidirectional"))
    )
    (net (code "79") (name "unconnected-(U1-PB6-Pad45)") (class "Default")
      (node (ref "U1") (pin "45") (pinfunction "PB6_45") (pintype "bidirectional"))
    )
    (net (code "80") (name "unconnected-(U1-PC15-OSC32_OUT-Pad3)") (class "Default")
      (node (ref "U1") (pin "3") (pinfunction "PC15-OSC32_OUT_3") (pintype "bidirectional"))
    )
    (net (code "81") (name "unconnected-(U1-PD1-Pad39)") (class "Default")
      (node (ref "U1") (pin "39") (pinfunction "PD1_39") (pintype "bidirectional"))
    )
  )
)
